# Ideal_Diode.net
KiCad netlist of a schematic drawn in Altium Designer
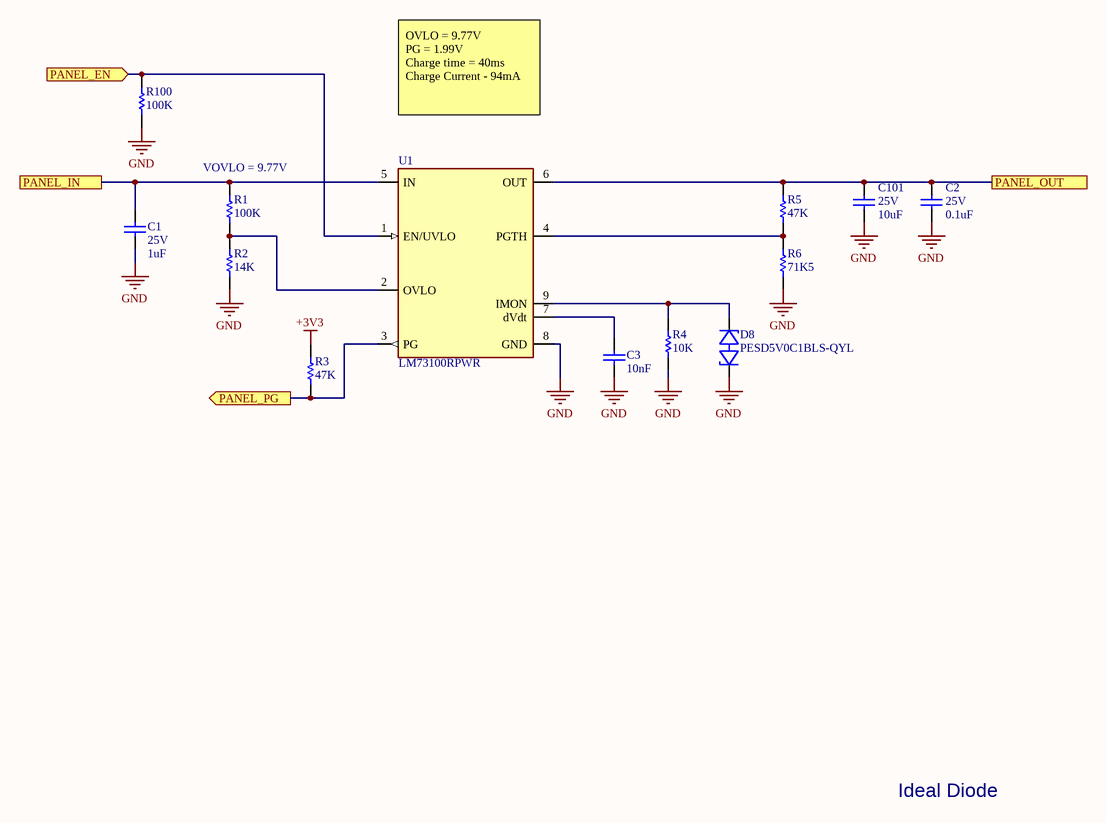
[diagram p0: Ideal_Diode.SchDoc]

(export (version "E")
  (design (tool "Eeschema 10.0.6"))
  (components
    (comp (ref "C1")
      (value "CL21B105KAFNNNE")
      (footprint "CAPC0805X060")
      (description "1uF ±10% 25V Ceramic Capacitor X7R 0805 (2012 Metric)")
      (fields
        (field (name "DISTRIBUTOR PART NUMBER") "1276-1066-1-ND")
        (field (name "TOLERANCE") "10%")
        (field (name "VOLTAGE RATING") "25V")
        (field (name "CAPACITANCE") "1uF")
      )
      (libsource (lib "Ahristi_Library") (part "CL21B105KAFNNNE"))
    )
    (comp (ref "C2")
      (value "CL21B104KACNNNC")
      (footprint "CAPC0805X060")
      (description "0.1uF ±10% 25V Ceramic Capacitor X7R 0805 (2012 Metric)")
      (fields
        (field (name "DISTRIBUTOR PART NUMBER") "1276-1099-1-ND")
        (field (name "TOLERANCE") "10%")
        (field (name "VOLTAGE RATING") "25V")
        (field (name "CAPACITANCE") "0.1uF")
      )
      (libsource (lib "Ahristi_Library") (part "CL21B104KACNNNC"))
    )
    (comp (ref "C3")
      (value "CL21B103KBANNNC")
      (footprint "CAPC0805X060")
      (description "10nF ±10% 50V Ceramic Capacitor X7R 0805 (2012 Metric)")
      (fields
        (field (name "DISTRIBUTOR PART NUMBER") "1276-1015-1-ND")
        (field (name "TOLERANCE") "10%")
        (field (name "CAPACITANCE") "10nF")
      )
      (libsource (lib "Ahristi_Library") (part "CL21B103KBANNNC"))
    )
    (comp (ref "C101")
      (value "GRM21BZ71E106KE15L")
      (footprint "CAPC0805X060")
      (description "10uF ±10% 25V Ceramic Capacitor X7R 0805 (2012 Metric)")
      (fields
        (field (name "DISTRIBUTOR PART NUMBER") "490-GRM21BZ71E106KE15LCT-ND")
        (field (name "TOLERANCE") "10%")
        (field (name "VOLTAGE RATING") "25V")
        (field (name "CAPACITANCE") "10uF")
      )
      (libsource (lib "Ahristi_Library") (part "GRM21BZ71E106KE15L"))
    )
    (comp (ref "D8")
      (value "PESD5V0C1BLS-QYL")
      (footprint "PESD5V0C1BLS-Q")
      (description "5.4V (Typ) Clamp 6.5A (8/20µs) Ipp Tvs Diode Surface Mount DFN1006BD-2")
      (fields (field (name "DISTRIBUTOR PART NUMBER") "1727-PESD5V0C1BLS-QYLCT-ND"))
      (libsource (lib "Ahristi_Library") (part "PESD5V0C1BLS-QYL"))
    )
    (comp (ref "R1")
      (value "RMCF0805FG100K")
      (footprint "RESC0805")
      (description "100 kOhms ±1% 0.125W, 1/8W Chip Resistor 0805 (2012 Metric) Automotive AEC-Q200 Thick Film")
      (fields
        (field (name "TOLERANCE") "1%")
        (field (name "DISTRIBUTOR PART NUMBER") "RMCF0805FG100KCT-ND")
        (field (name "RESISTANCE") "100K")
      )
      (libsource (lib "Ahristi_Library") (part "RMCF0805FG100K"))
    )
    (comp (ref "R2")
      (value "RMCF0805FT14K0")
      (footprint "RESC0805")
      (description "14 kOhms ±1% 0.125W, 1/8W Chip Resistor 0805 (2012 Metric) Automotive AEC-Q200 Thick Film")
      (fields
        (field (name "TOLERANCE") "1%")
        (field (name "DISTRIBUTOR PART NUMBER") "RMCF0805FT14K0CT-ND")
        (field (name "RESISTANCE") "14K")
      )
      (libsource (lib "Ahristi_Library") (part "RMCF0805FT14K0"))
    )
    (comp (ref "R3")
      (value "RMCF0805FT47K0")
      (footprint "RESC0805")
      (description "47 kOhms ±1% 0.125W, 1/8W Chip Resistor 0805 (2012 Metric) Automotive AEC-Q200 Thick Film")
      (fields
        (field (name "TOLERANCE") "1%")
        (field (name "DISTRIBUTOR PART NUMBER") "RMCF0805FT47K0CT-ND")
        (field (name "RESISTANCE") "47K")
      )
      (libsource (lib "Ahristi_Library") (part "RMCF0805FT47K0"))
    )
    (comp (ref "R4")
      (value "RMCF0805FT10K0")
      (footprint "RESC0805")
      (description "10 kOhms ±1% 0.125W, 1/8W Chip Resistor 0805 (2012 Metric) Automotive AEC-Q200 Thick Film")
      (fields
        (field (name "TOLERANCE") "1%")
        (field (name "DISTRIBUTOR PART NUMBER") "RMCF0805FT10K0CT-ND")
        (field (name "RESISTANCE") "10K")
      )
      (libsource (lib "Ahristi_Library") (part "RMCF0805FT10K0"))
    )
    (comp (ref "R5")
      (value "RMCF0805FT47K0")
      (footprint "RESC0805")
      (description "47 kOhms ±1% 0.125W, 1/8W Chip Resistor 0805 (2012 Metric) Automotive AEC-Q200 Thick Film")
      (fields
        (field (name "TOLERANCE") "1%")
        (field (name "DISTRIBUTOR PART NUMBER") "RMCF0805FT47K0CT-ND")
        (field (name "RESISTANCE") "47K")
      )
      (libsource (lib "Ahristi_Library") (part "RMCF0805FT47K0"))
    )
    (comp (ref "R6")
      (value "RMCF0805FT71K5")
      (footprint "RESC0805")
      (description "71.5 kOhms ±1% 0.125W, 1/8W Chip Resistor 0805 (2012 Metric) Automotive AEC-Q200 Thick Film")
      (fields
        (field (name "TOLERANCE") "1%")
        (field (name "DISTRIBUTOR PART NUMBER") "RMCF0805FT71K5CT-ND")
        (field (name "RESISTANCE") "71K5")
      )
      (libsource (lib "Ahristi_Library") (part "RMCF0805FT71K5"))
    )
    (comp (ref "R100")
      (value "RMCF0805FG100K")
      (footprint "RESC0805")
      (description "100 kOhms ±1% 0.125W, 1/8W Chip Resistor 0805 (2012 Metric) Automotive AEC-Q200 Thick Film")
      (fields
        (field (name "TOLERANCE") "1%")
        (field (name "DISTRIBUTOR PART NUMBER") "RMCF0805FG100KCT-ND")
        (field (name "RESISTANCE") "100K")
      )
      (libsource (lib "Ahristi_Library") (part "RMCF0805FG100K"))
    )
    (comp (ref "U1")
      (value "LM73100RPWR")
      (footprint "VFQFN-10")
      (description "Ideal Diode 2.7 - 23 V, 5.5 A with Input Reverse Polarity and\r\nOvervoltage Protection")
      (fields (field (name "DISTRIBUTOR PART NUMBER") "296-LM73100RPWRCT-ND"))
      (libsource (lib "Ahristi_Library") (part "LM73100RPWR"))
    )
  )
  (nets
    (net (code "1") (name "+3V3") (class "Default")
      (node (ref "R3") (pin "2") (pinfunction "2_2") (pintype "passive"))
    )
    (net (code "2") (name "/PANEL_EN") (class "Default")
      (node (ref "R100") (pin "2") (pinfunction "2_2") (pintype "passive"))
      (node (ref "U1") (pin "1") (pinfunction "EN/UVLO_1") (pintype "input"))
    )
    (net (code "3") (name "/PANEL_IN") (class "Default")
      (node (ref "C1") (pin "2") (pinfunction "2_2") (pintype "passive"))
      (node (ref "R1") (pin "2") (pinfunction "2_2") (pintype "passive"))
      (node (ref "U1") (pin "5") (pinfunction "IN_5") (pintype "passive"))
    )
    (net (code "4") (name "/PANEL_OUT") (class "Default")
      (node (ref "C101") (pin "2") (pinfunction "2_2") (pintype "passive"))
      (node (ref "C2") (pin "2") (pinfunction "2_2") (pintype "passive"))
      (node (ref "R5") (pin "2") (pinfunction "2_2") (pintype "passive"))
      (node (ref "U1") (pin "6") (pinfunction "OUT_6") (pintype "passive"))
    )
    (net (code "5") (name "/PANEL_PG") (class "Default")
      (node (ref "R3") (pin "1") (pinfunction "1_1") (pintype "passive"))
      (node (ref "U1") (pin "3") (pinfunction "PG_3") (pintype "output"))
    )
    (net (code "6") (name "GND") (class "Default")
      (node (ref "C1") (pin "1") (pinfunction "1_1") (pintype "passive"))
      (node (ref "C101") (pin "1") (pinfunction "1_1") (pintype "passive"))
      (node (ref "C2") (pin "1") (pinfunction "1_1") (pintype "passive"))
      (node (ref "C3") (pin "1") (pinfunction "1_1") (pintype "passive"))
      (node (ref "D8") (pin "1") (pinfunction "1_1") (pintype "passive"))
      (node (ref "R100") (pin "1") (pinfunction "1_1") (pintype "passive"))
      (node (ref "R2") (pin "1") (pinfunction "1_1") (pintype "passive"))
      (node (ref "R4") (pin "1") (pinfunction "1_1") (pintype "passive"))
      (node (ref "R6") (pin "1") (pinfunction "1_1") (pintype "passive"))
      (node (ref "U1") (pin "8") (pinfunction "GND_8") (pintype "passive"))
    )
    (net (code "7") (name "Net-(U1-IMON)") (class "Default")
      (node (ref "D8") (pin "2") (pinfunction "2_2") (pintype "passive"))
      (node (ref "R4") (pin "2") (pinfunction "2_2") (pintype "passive"))
      (node (ref "U1") (pin "9") (pinfunction "IMON_9") (pintype "passive"))
    )
    (net (code "8") (name "Net-(U1-OVLO)") (class "Default")
      (node (ref "R1") (pin "1") (pinfunction "1_1") (pintype "passive"))
      (node (ref "R2") (pin "2") (pinfunction "2_2") (pintype "passive"))
      (node (ref "U1") (pin "2") (pinfunction "OVLO_2") (pintype "passive"))
    )
    (net (code "9") (name "Net-(U1-PGTH)") (class "Default")
      (node (ref "R5") (pin "1") (pinfunction "1_1") (pintype "passive"))
      (node (ref "R6") (pin "2") (pinfunction "2_2") (pintype "passive"))
      (node (ref "U1") (pin "4") (pinfunction "PGTH_4") (pintype "passive"))
    )
    (net (code "10") (name "Net-(U1-dVdt)") (class "Default")
      (node (ref "C3") (pin "2") (pinfunction "2_2") (pintype "passive"))
      (node (ref "U1") (pin "7") (pinfunction "dVdt_7") (pintype "passive"))
    )
  )
)
